# control_0_1.net
KiCad netlist of a schematic drawn in Altium Designer
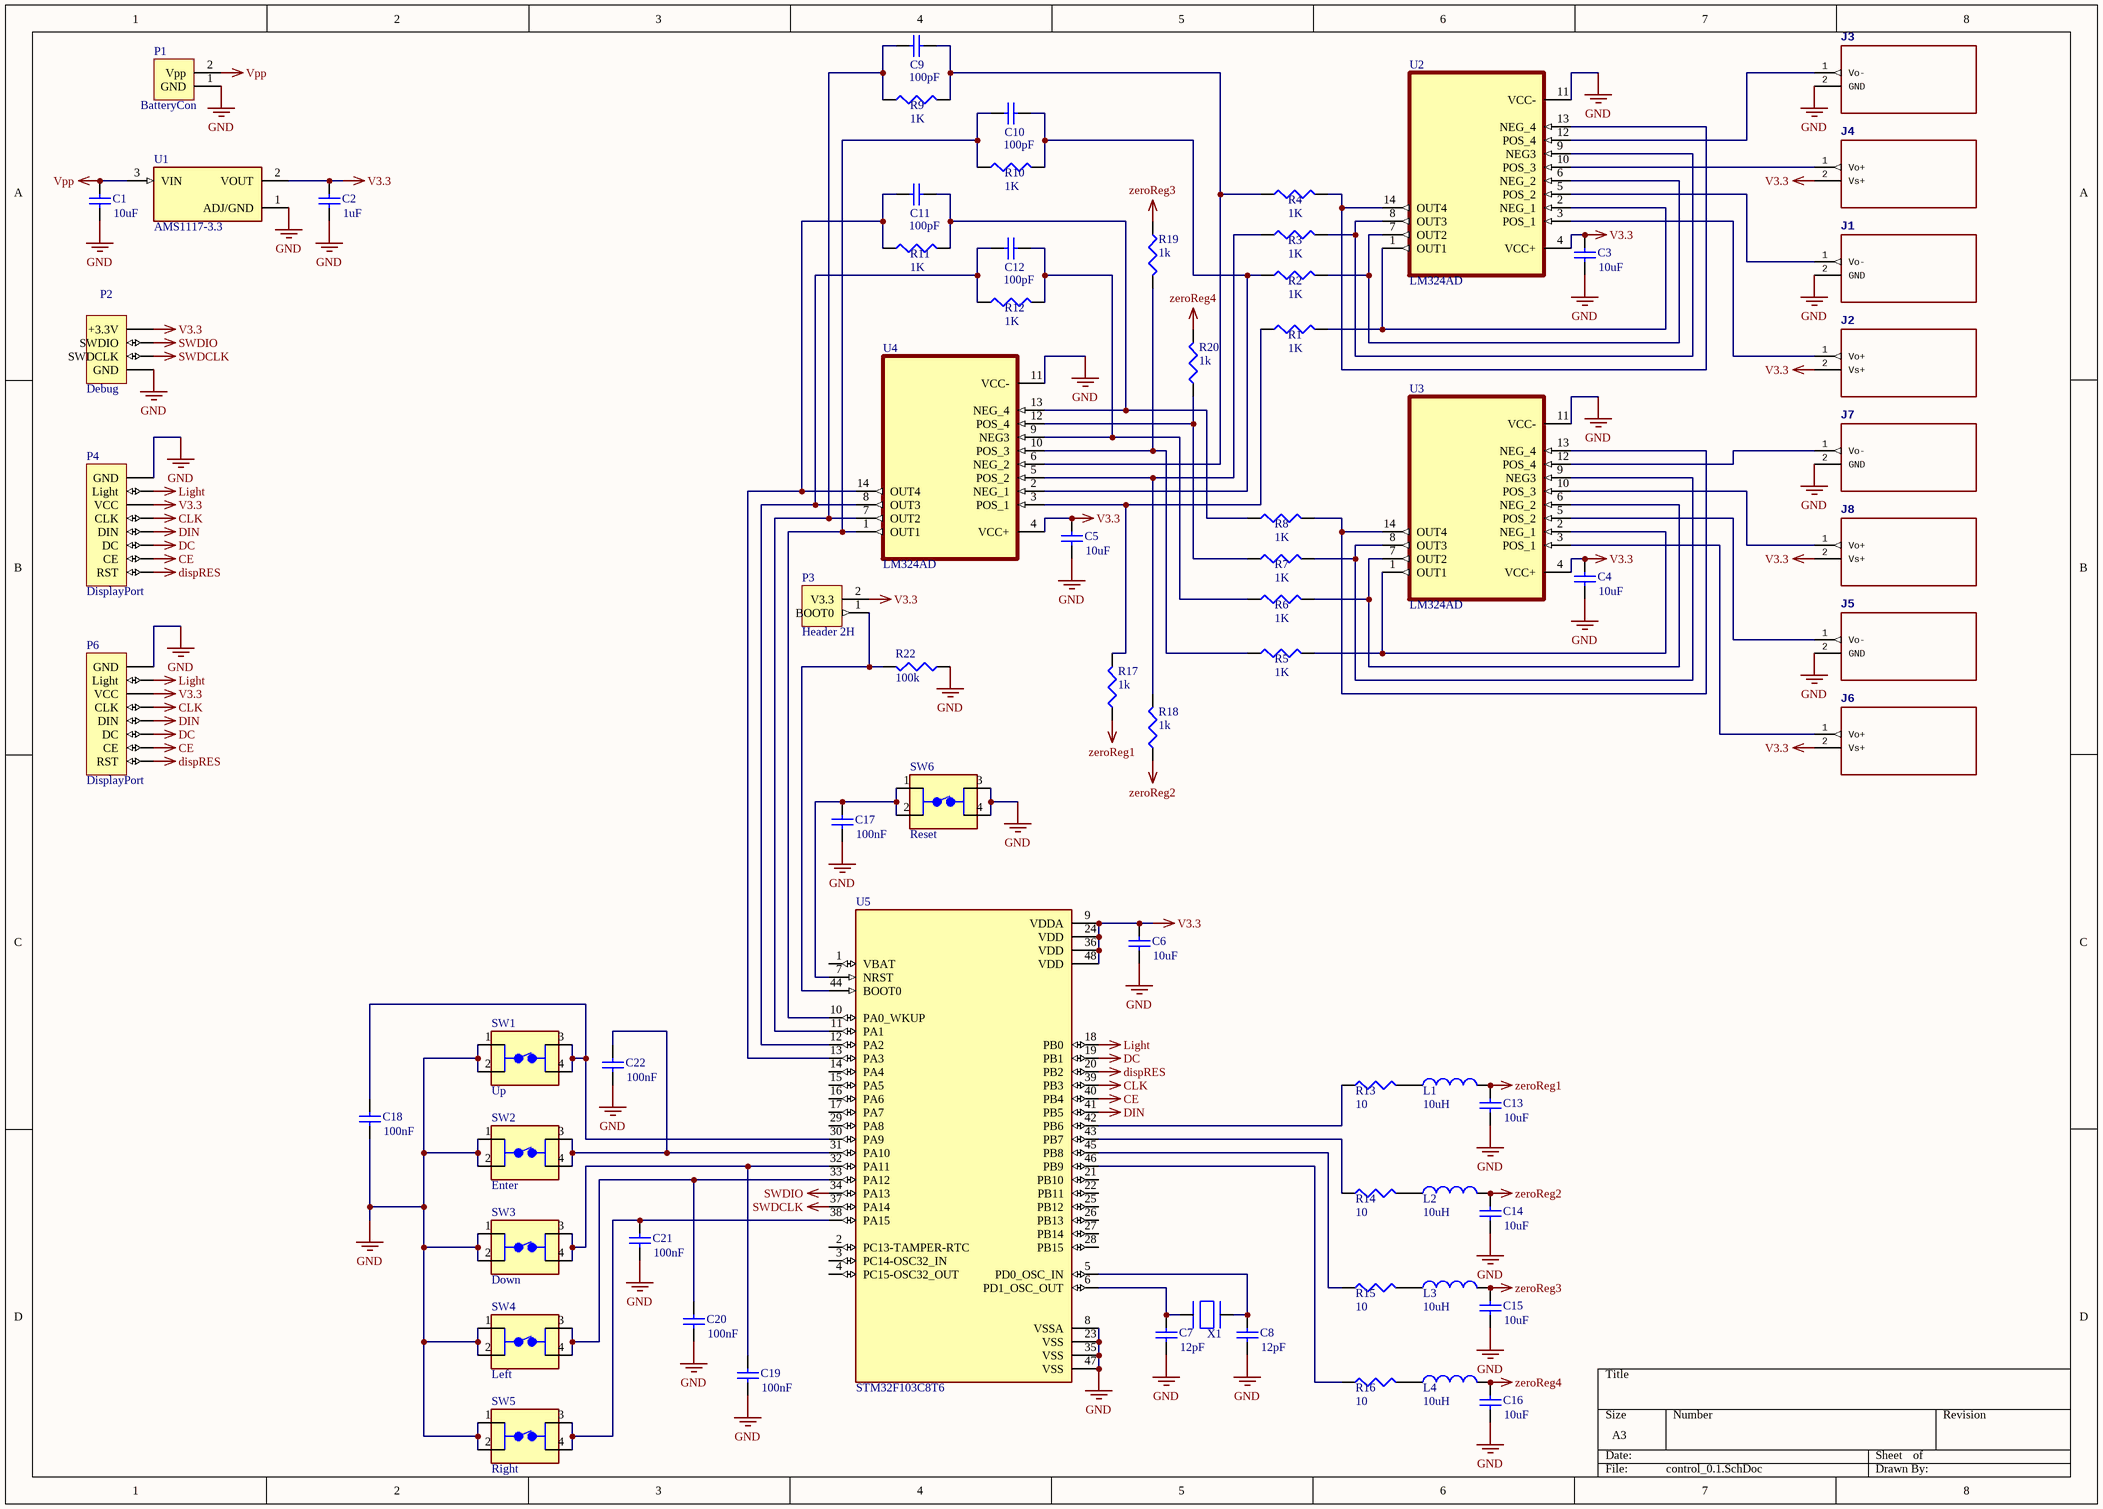
[diagram p0: control_0.1.SchDoc]

(export (version "E")
  (design (tool "Eeschema 10.0.6"))
  (components
    (comp (ref "C1")
      (value "10uF")
      (footprint "C1206")
      (description "Capacitor (Semiconductor SIM Model)")
      (fields (field (name "Comment") "Cap Semi") (field (name "PUBLISHER") "Altium Limited"))
      (libsource (lib "Miscellaneous Devices") (part "Cap Semi"))
    )
    (comp (ref "C2")
      (value "1uF")
      (footprint "C1206")
      (description "Capacitor (Semiconductor SIM Model)")
      (fields (field (name "Comment") "Cap Semi") (field (name "PUBLISHER") "Altium Limited"))
      (libsource (lib "Miscellaneous Devices") (part "Cap Semi"))
    )
    (comp (ref "C3")
      (value "10uF")
      (footprint "C1206")
      (description "Capacitor (Semiconductor SIM Model)")
      (fields (field (name "Comment") "Cap Semi") (field (name "PUBLISHER") "Altium Limited"))
      (libsource (lib "Miscellaneous Devices") (part "Cap Semi"))
    )
    (comp (ref "C4")
      (value "10uF")
      (footprint "C1206")
      (description "Capacitor (Semiconductor SIM Model)")
      (fields (field (name "Comment") "Cap Semi") (field (name "PUBLISHER") "Altium Limited"))
      (libsource (lib "Miscellaneous Devices") (part "Cap Semi"))
    )
    (comp (ref "C5")
      (value "10uF")
      (footprint "C1206")
      (description "Capacitor (Semiconductor SIM Model)")
      (fields (field (name "Comment") "Cap Semi") (field (name "PUBLISHER") "Altium Limited"))
      (libsource (lib "Miscellaneous Devices") (part "Cap Semi"))
    )
    (comp (ref "C6")
      (value "10uF")
      (footprint "C1206")
      (description "Capacitor (Semiconductor SIM Model)")
      (fields (field (name "Comment") "Cap Semi") (field (name "PUBLISHER") "Altium Limited"))
      (libsource (lib "Miscellaneous Devices") (part "Cap Semi"))
    )
    (comp (ref "C7")
      (value "12pF")
      (footprint "C1206")
      (description "Capacitor (Semiconductor SIM Model)")
      (fields (field (name "Comment") "Cap Semi") (field (name "PUBLISHER") "Altium Limited"))
      (libsource (lib "Miscellaneous Devices") (part "Cap Semi"))
    )
    (comp (ref "C8")
      (value "12pF")
      (footprint "C1206")
      (description "Capacitor (Semiconductor SIM Model)")
      (fields (field (name "Comment") "Cap Semi") (field (name "PUBLISHER") "Altium Limited"))
      (libsource (lib "Miscellaneous Devices") (part "Cap Semi"))
    )
    (comp (ref "C9")
      (value "100pF")
      (footprint "C1206")
      (description "Capacitor (Semiconductor SIM Model)")
      (fields (field (name "Comment") "Cap Semi") (field (name "PUBLISHER") "Altium Limited"))
      (libsource (lib "Miscellaneous Devices") (part "Cap Semi"))
    )
    (comp (ref "C10")
      (value "100pF")
      (footprint "C1206")
      (description "Capacitor (Semiconductor SIM Model)")
      (fields (field (name "Comment") "Cap Semi") (field (name "PUBLISHER") "Altium Limited"))
      (libsource (lib "Miscellaneous Devices") (part "Cap Semi"))
    )
    (comp (ref "C11")
      (value "100pF")
      (footprint "C1206")
      (description "Capacitor (Semiconductor SIM Model)")
      (fields (field (name "Comment") "Cap Semi") (field (name "PUBLISHER") "Altium Limited"))
      (libsource (lib "Miscellaneous Devices") (part "Cap Semi"))
    )
    (comp (ref "C12")
      (value "100pF")
      (footprint "C1206")
      (description "Capacitor (Semiconductor SIM Model)")
      (fields (field (name "Comment") "Cap Semi") (field (name "PUBLISHER") "Altium Limited"))
      (libsource (lib "Miscellaneous Devices") (part "Cap Semi"))
    )
    (comp (ref "C13")
      (value "10uF")
      (footprint "C1206")
      (description "Capacitor (Semiconductor SIM Model)")
      (fields (field (name "Comment") "Cap Semi") (field (name "PUBLISHER") "Altium Limited"))
      (libsource (lib "Miscellaneous Devices") (part "Cap Semi"))
    )
    (comp (ref "C14")
      (value "10uF")
      (footprint "C1206")
      (description "Capacitor (Semiconductor SIM Model)")
      (fields (field (name "Comment") "Cap Semi") (field (name "PUBLISHER") "Altium Limited"))
      (libsource (lib "Miscellaneous Devices") (part "Cap Semi"))
    )
    (comp (ref "C15")
      (value "10uF")
      (footprint "C1206")
      (description "Capacitor (Semiconductor SIM Model)")
      (fields (field (name "Comment") "Cap Semi") (field (name "PUBLISHER") "Altium Limited"))
      (libsource (lib "Miscellaneous Devices") (part "Cap Semi"))
    )
    (comp (ref "C16")
      (value "10uF")
      (footprint "C1206")
      (description "Capacitor (Semiconductor SIM Model)")
      (fields (field (name "Comment") "Cap Semi") (field (name "PUBLISHER") "Altium Limited"))
      (libsource (lib "Miscellaneous Devices") (part "Cap Semi"))
    )
    (comp (ref "C17")
      (value "100nF")
      (footprint "C1206")
      (description "Capacitor (Semiconductor SIM Model)")
      (fields (field (name "Comment") "Cap Semi") (field (name "PUBLISHER") "Altium Limited"))
      (libsource (lib "Miscellaneous Devices") (part "Cap Semi"))
    )
    (comp (ref "C18")
      (value "100nF")
      (footprint "C1206")
      (description "Capacitor (Semiconductor SIM Model)")
      (fields (field (name "Comment") "Cap Semi") (field (name "PUBLISHER") "Altium Limited"))
      (libsource (lib "Miscellaneous Devices") (part "Cap Semi"))
    )
    (comp (ref "C19")
      (value "100nF")
      (footprint "C1206")
      (description "Capacitor (Semiconductor SIM Model)")
      (fields (field (name "Comment") "Cap Semi") (field (name "PUBLISHER") "Altium Limited"))
      (libsource (lib "Miscellaneous Devices") (part "Cap Semi"))
    )
    (comp (ref "C20")
      (value "100nF")
      (footprint "C1206")
      (description "Capacitor (Semiconductor SIM Model)")
      (fields (field (name "Comment") "Cap Semi") (field (name "PUBLISHER") "Altium Limited"))
      (libsource (lib "Miscellaneous Devices") (part "Cap Semi"))
    )
    (comp (ref "C21")
      (value "100nF")
      (footprint "C1206")
      (description "Capacitor (Semiconductor SIM Model)")
      (fields (field (name "Comment") "Cap Semi") (field (name "PUBLISHER") "Altium Limited"))
      (libsource (lib "Miscellaneous Devices") (part "Cap Semi"))
    )
    (comp (ref "C22")
      (value "100nF")
      (footprint "C1206")
      (description "Capacitor (Semiconductor SIM Model)")
      (fields (field (name "Comment") "Cap Semi") (field (name "PUBLISHER") "Altium Limited"))
      (libsource (lib "Miscellaneous Devices") (part "Cap Semi"))
    )
    (comp (ref "J1")
      (value "SAMTEC-A-TSM-102-01-L-SHJ")
      (footprint "SAMTEC-A-TSM-102-01-L-SH")
      (libsource (lib "SAMTEC-A-TSM-102-01-L-SH") (part "SAMTEC-A-TSM-102-01-L-SHJ"))
    )
    (comp (ref "J2")
      (value "SAMTEC-A-TSM-102-01-L-SHJ")
      (footprint "SAMTEC-A-TSM-102-01-L-SH")
      (libsource (lib "SAMTEC-A-TSM-102-01-L-SH") (part "SAMTEC-A-TSM-102-01-L-SHJ"))
    )
    (comp (ref "J3")
      (value "SAMTEC-A-TSM-102-01-L-SHJ")
      (footprint "SAMTEC-A-TSM-102-01-L-SH")
      (libsource (lib "SAMTEC-A-TSM-102-01-L-SH") (part "SAMTEC-A-TSM-102-01-L-SHJ"))
    )
    (comp (ref "J4")
      (value "SAMTEC-A-TSM-102-01-L-SHJ")
      (footprint "SAMTEC-A-TSM-102-01-L-SH")
      (libsource (lib "SAMTEC-A-TSM-102-01-L-SH") (part "SAMTEC-A-TSM-102-01-L-SHJ"))
    )
    (comp (ref "J5")
      (value "SAMTEC-A-TSM-102-01-L-SHJ")
      (footprint "SAMTEC-A-TSM-102-01-L-SH")
      (libsource (lib "SAMTEC-A-TSM-102-01-L-SH") (part "SAMTEC-A-TSM-102-01-L-SHJ"))
    )
    (comp (ref "J6")
      (value "SAMTEC-A-TSM-102-01-L-SHJ")
      (footprint "SAMTEC-A-TSM-102-01-L-SH")
      (libsource (lib "SAMTEC-A-TSM-102-01-L-SH") (part "SAMTEC-A-TSM-102-01-L-SHJ"))
    )
    (comp (ref "J7")
      (value "SAMTEC-A-TSM-102-01-L-SHJ")
      (footprint "SAMTEC-A-TSM-102-01-L-SH")
      (libsource (lib "SAMTEC-A-TSM-102-01-L-SH") (part "SAMTEC-A-TSM-102-01-L-SHJ"))
    )
    (comp (ref "J8")
      (value "SAMTEC-A-TSM-102-01-L-SHJ")
      (footprint "SAMTEC-A-TSM-102-01-L-SH")
      (libsource (lib "SAMTEC-A-TSM-102-01-L-SH") (part "SAMTEC-A-TSM-102-01-L-SHJ"))
    )
    (comp (ref "L1")
      (value "10uH")
      (footprint "INDC1608L")
      (description "Inductor")
      (fields (field (name "PUBLISHER") "Altium Limited"))
      (libsource (lib "Miscellaneous Devices") (part "Inductor"))
    )
    (comp (ref "L2")
      (value "10uH")
      (footprint "INDC1608L")
      (description "Inductor")
      (fields (field (name "PUBLISHER") "Altium Limited"))
      (libsource (lib "Miscellaneous Devices") (part "Inductor"))
    )
    (comp (ref "L3")
      (value "10uH")
      (footprint "INDC1608L")
      (description "Inductor")
      (fields (field (name "PUBLISHER") "Altium Limited"))
      (libsource (lib "Miscellaneous Devices") (part "Inductor"))
    )
    (comp (ref "L4")
      (value "10uH")
      (footprint "INDC1608L")
      (description "Inductor")
      (fields (field (name "PUBLISHER") "Altium Limited"))
      (libsource (lib "Miscellaneous Devices") (part "Inductor"))
    )
    (comp (ref "P1")
      (value "BatteryCon")
      (footprint "HDR1X2H")
      (description "Header, 2-Pin, Right Angle")
      (fields (field (name "PUBLISHER") "Altium Limited"))
      (libsource (lib "Miscellaneous Connectors") (part "Header 2H"))
    )
    (comp (ref "P2")
      (value "Debug")
      (footprint "HDR1X4H")
      (description "Header, 4-Pin, Right Angle")
      (fields (field (name "PUBLISHER") "Altium Limited"))
      (libsource (lib "Miscellaneous Connectors") (part "Header 4H"))
    )
    (comp (ref "P3")
      (value "Header 2H")
      (footprint "HDR1X2H")
      (description "Header, 2-Pin, Right Angle")
      (fields (field (name "PUBLISHER") "Altium Limited"))
      (libsource (lib "Miscellaneous Connectors") (part "Header 2H"))
    )
    (comp (ref "P4")
      (value "DisplayPort")
      (footprint "HDR1X8")
      (description "Header, 8-Pin")
      (fields (field (name "PUBLISHER") "Altium Limited"))
      (libsource (lib "Miscellaneous Connectors") (part "Header 8"))
    )
    (comp (ref "P6")
      (value "DisplayPort")
      (footprint "HDR1X8")
      (description "Header, 8-Pin")
      (fields (field (name "PUBLISHER") "Altium Limited"))
      (libsource (lib "Miscellaneous Connectors") (part "Header 8"))
    )
    (comp (ref "R1")
      (value "1K")
      (footprint "14-1210")
      (description "Resistor")
      (fields (field (name "Comment") "Res3") (field (name "PUBLISHER") "Altium Limited"))
      (libsource (lib "Miscellaneous Devices") (part "Res3"))
    )
    (comp (ref "R2")
      (value "1K")
      (footprint "14-1210")
      (description "Resistor")
      (fields (field (name "Comment") "Res3") (field (name "PUBLISHER") "Altium Limited"))
      (libsource (lib "Miscellaneous Devices") (part "Res3"))
    )
    (comp (ref "R3")
      (value "1K")
      (footprint "14-1210")
      (description "Resistor")
      (fields (field (name "Comment") "Res3") (field (name "PUBLISHER") "Altium Limited"))
      (libsource (lib "Miscellaneous Devices") (part "Res3"))
    )
    (comp (ref "R4")
      (value "1K")
      (footprint "14-1210")
      (description "Resistor")
      (fields (field (name "Comment") "Res3") (field (name "PUBLISHER") "Altium Limited"))
      (libsource (lib "Miscellaneous Devices") (part "Res3"))
    )
    (comp (ref "R5")
      (value "1K")
      (footprint "14-1210")
      (description "Resistor")
      (fields (field (name "Comment") "Res3") (field (name "PUBLISHER") "Altium Limited"))
      (libsource (lib "Miscellaneous Devices") (part "Res3"))
    )
    (comp (ref "R6")
      (value "1K")
      (footprint "14-1210")
      (description "Resistor")
      (fields (field (name "Comment") "Res3") (field (name "PUBLISHER") "Altium Limited"))
      (libsource (lib "Miscellaneous Devices") (part "Res3"))
    )
    (comp (ref "R7")
      (value "1K")
      (footprint "14-1210")
      (description "Resistor")
      (fields (field (name "Comment") "Res3") (field (name "PUBLISHER") "Altium Limited"))
      (libsource (lib "Miscellaneous Devices") (part "Res3"))
    )
    (comp (ref "R8")
      (value "1K")
      (footprint "14-1210")
      (description "Resistor")
      (fields (field (name "Comment") "Res3") (field (name "PUBLISHER") "Altium Limited"))
      (libsource (lib "Miscellaneous Devices") (part "Res3"))
    )
    (comp (ref "R9")
      (value "1K")
      (footprint "14-1210")
      (description "Resistor")
      (fields (field (name "Comment") "Res3") (field (name "PUBLISHER") "Altium Limited"))
      (libsource (lib "Miscellaneous Devices") (part "Res3"))
    )
    (comp (ref "R10")
      (value "1K")
      (footprint "14-1210")
      (description "Resistor")
      (fields (field (name "Comment") "Res3") (field (name "PUBLISHER") "Altium Limited"))
      (libsource (lib "Miscellaneous Devices") (part "Res3"))
    )
    (comp (ref "R11")
      (value "1K")
      (footprint "14-1210")
      (description "Resistor")
      (fields (field (name "Comment") "Res3") (field (name "PUBLISHER") "Altium Limited"))
      (libsource (lib "Miscellaneous Devices") (part "Res3"))
    )
    (comp (ref "R12")
      (value "1K")
      (footprint "14-1210")
      (description "Resistor")
      (fields (field (name "Comment") "Res3") (field (name "PUBLISHER") "Altium Limited"))
      (libsource (lib "Miscellaneous Devices") (part "Res3"))
    )
    (comp (ref "R13")
      (value "10")
      (footprint "14-1210")
      (description "Resistor")
      (fields (field (name "Comment") "Res3") (field (name "PUBLISHER") "Altium Limited"))
      (libsource (lib "Miscellaneous Devices") (part "Res3"))
    )
    (comp (ref "R14")
      (value "10")
      (footprint "14-1210")
      (description "Resistor")
      (fields (field (name "Comment") "Res3") (field (name "PUBLISHER") "Altium Limited"))
      (libsource (lib "Miscellaneous Devices") (part "Res3"))
    )
    (comp (ref "R15")
      (value "10")
      (footprint "14-1210")
      (description "Resistor")
      (fields (field (name "Comment") "Res3") (field (name "PUBLISHER") "Altium Limited"))
      (libsource (lib "Miscellaneous Devices") (part "Res3"))
    )
    (comp (ref "R16")
      (value "10")
      (footprint "14-1210")
      (description "Resistor")
      (fields (field (name "Comment") "Res3") (field (name "PUBLISHER") "Altium Limited"))
      (libsource (lib "Miscellaneous Devices") (part "Res3"))
    )
    (comp (ref "R17")
      (value "1k")
      (footprint "14-1210")
      (description "Resistor")
      (fields (field (name "Comment") "Res3") (field (name "PUBLISHER") "Altium Limited"))
      (libsource (lib "Miscellaneous Devices") (part "Res3"))
    )
    (comp (ref "R18")
      (value "1k")
      (footprint "14-1210")
      (description "Resistor")
      (fields (field (name "Comment") "Res3") (field (name "PUBLISHER") "Altium Limited"))
      (libsource (lib "Miscellaneous Devices") (part "Res3"))
    )
    (comp (ref "R19")
      (value "1k")
      (footprint "14-1210")
      (description "Resistor")
      (fields (field (name "Comment") "Res3") (field (name "PUBLISHER") "Altium Limited"))
      (libsource (lib "Miscellaneous Devices") (part "Res3"))
    )
    (comp (ref "R20")
      (value "1k")
      (footprint "14-1210")
      (description "Resistor")
      (fields (field (name "Comment") "Res3") (field (name "PUBLISHER") "Altium Limited"))
      (libsource (lib "Miscellaneous Devices") (part "Res3"))
    )
    (comp (ref "R22")
      (value "100k")
      (footprint "14-1210")
      (description "Resistor")
      (fields (field (name "Comment") "Res3") (field (name "PUBLISHER") "Altium Limited"))
      (libsource (lib "Miscellaneous Devices") (part "Res3"))
    )
    (comp (ref "SW1")
      (value "Up")
      (footprint "TE_FSM4JSMA")
      (description "Tactile Switch SPST-NO Top Actuated Surface Mount")
      (fields (field (name "MP") "FSM4JSMA") (field (name "MF") "TE Connectivity"))
      (libsource (lib "FSM4JSMA") (part "FSM4JSMA"))
    )
    (comp (ref "SW2")
      (value "Enter")
      (footprint "TE_FSM4JSMA")
      (description "Tactile Switch SPST-NO Top Actuated Surface Mount")
      (fields (field (name "MP") "FSM4JSMA") (field (name "MF") "TE Connectivity"))
      (libsource (lib "FSM4JSMA") (part "FSM4JSMA"))
    )
    (comp (ref "SW3")
      (value "Down")
      (footprint "TE_FSM4JSMA")
      (description "Tactile Switch SPST-NO Top Actuated Surface Mount")
      (fields (field (name "MP") "FSM4JSMA") (field (name "MF") "TE Connectivity"))
      (libsource (lib "FSM4JSMA") (part "FSM4JSMA"))
    )
    (comp (ref "SW4")
      (value "Left")
      (footprint "TE_FSM4JSMA")
      (description "Tactile Switch SPST-NO Top Actuated Surface Mount")
      (fields (field (name "MP") "FSM4JSMA") (field (name "MF") "TE Connectivity"))
      (libsource (lib "FSM4JSMA") (part "FSM4JSMA"))
    )
    (comp (ref "SW5")
      (value "Right")
      (footprint "TE_FSM4JSMA")
      (description "Tactile Switch SPST-NO Top Actuated Surface Mount")
      (fields (field (name "MP") "FSM4JSMA") (field (name "MF") "TE Connectivity"))
      (libsource (lib "FSM4JSMA") (part "FSM4JSMA"))
    )
    (comp (ref "SW6")
      (value "Reset")
      (footprint "TE_FSM4JSMA")
      (description "Tactile Switch SPST-NO Top Actuated Surface Mount")
      (fields (field (name "MP") "FSM4JSMA") (field (name "MF") "TE Connectivity"))
      (libsource (lib "FSM4JSMA") (part "FSM4JSMA"))
    )
    (comp (ref "U1")
      (value "AMS1117-3.3")
      (footprint "SOT229P700X180-4N")
      (description "Sot223/Pkg 1-Amp 3.3-Volt Low Drop Out Voltage Regulatator")
      (fields (field (name "MF") "Advanced Monolithic Systems"))
      (libsource (lib "AMS1117-3.3") (part "AMS1117-3.3"))
    )
    (comp (ref "U2")
      (value "LM324AD")
      (footprint "SOIC127P600X175-14N")
      (description "Op Amp Quad Low Power Amplifier Â±15V/30V 14-Pin SOIC Tube")
      (fields (field (name "MF") "Texas Instruments"))
      (libsource (lib "LM324AD") (part "LM324AD"))
    )
    (comp (ref "U3")
      (value "LM324AD")
      (footprint "SOIC127P600X175-14N")
      (description "Op Amp Quad Low Power Amplifier Â±15V/30V 14-Pin SOIC Tube")
      (fields (field (name "MF") "Texas Instruments"))
      (libsource (lib "LM324AD") (part "LM324AD"))
    )
    (comp (ref "U4")
      (value "LM324AD")
      (footprint "SOIC127P600X175-14N")
      (description "Op Amp Quad Low Power Amplifier Â±15V/30V 14-Pin SOIC Tube")
      (fields (field (name "MF") "Texas Instruments"))
      (libsource (lib "LM324AD") (part "LM324AD"))
    )
    (comp (ref "U5")
      (value "STM32F103C8T6")
      (footprint "QFP50P900X900X160-48N")
      (description "ARMÂ® CortexÂ®-M3 STM32F1 Microcontroller IC 32-Bit 72MHz 64KB _64K x 8_ FLASH")
      (fields (field (name "MF") "STMicroelectronics"))
      (libsource (lib "STM32F103C8T6") (part "STM32F103C8T6"))
    )
    (comp (ref "X1")
      (value "ABLS-8.000MHZ-B4-T")
      (footprint "HC-49/US")
      (description "8MHz Â±30ppm Crystal 18pF 80 Ohms HC-49/US")
      (fields (field (name "MF") "Abracon LLC"))
      (libsource (lib "ABLS-8.000MHZ-B4-T") (part "ABLS-8.000MHZ-B4-T"))
    )
  )
  (nets
    (net (code "1") (name "CE") (class "Default")
      (node (ref "P4") (pin "2") (pinfunction "CE_2") (pintype "bidirectional"))
      (node (ref "P6") (pin "2") (pinfunction "CE_2") (pintype "bidirectional"))
      (node (ref "U5") (pin "40") (pinfunction "PB4_40") (pintype "bidirectional"))
    )
    (net (code "2") (name "CLK") (class "Default")
      (node (ref "P4") (pin "5") (pinfunction "CLK_5") (pintype "bidirectional"))
      (node (ref "P6") (pin "5") (pinfunction "CLK_5") (pintype "bidirectional"))
      (node (ref "U5") (pin "39") (pinfunction "PB3_39") (pintype "bidirectional"))
    )
    (net (code "3") (name "DC") (class "Default")
      (node (ref "P4") (pin "3") (pinfunction "DC_3") (pintype "bidirectional"))
      (node (ref "P6") (pin "3") (pinfunction "DC_3") (pintype "bidirectional"))
      (node (ref "U5") (pin "19") (pinfunction "PB1_19") (pintype "bidirectional"))
    )
    (net (code "4") (name "DIN") (class "Default")
      (node (ref "P4") (pin "4") (pinfunction "DIN_4") (pintype "bidirectional"))
      (node (ref "P6") (pin "4") (pinfunction "DIN_4") (pintype "bidirectional"))
      (node (ref "U5") (pin "41") (pinfunction "PB5_41") (pintype "bidirectional"))
    )
    (net (code "5") (name "GND") (class "Default")
      (node (ref "C1") (pin "1") (pinfunction "1_1") (pintype "passive"))
      (node (ref "C13") (pin "1") (pinfunction "1_1") (pintype "passive"))
      (node (ref "C14") (pin "1") (pinfunction "1_1") (pintype "passive"))
      (node (ref "C15") (pin "1") (pinfunction "1_1") (pintype "passive"))
      (node (ref "C16") (pin "1") (pinfunction "1_1") (pintype "passive"))
      (node (ref "C17") (pin "1") (pinfunction "1_1") (pintype "passive"))
      (node (ref "C18") (pin "1") (pinfunction "1_1") (pintype "passive"))
      (node (ref "C19") (pin "1") (pinfunction "1_1") (pintype "passive"))
      (node (ref "C2") (pin "1") (pinfunction "1_1") (pintype "passive"))
      (node (ref "C20") (pin "1") (pinfunction "1_1") (pintype "passive"))
      (node (ref "C21") (pin "1") (pinfunction "1_1") (pintype "passive"))
      (node (ref "C22") (pin "1") (pinfunction "1_1") (pintype "passive"))
      (node (ref "C3") (pin "1") (pinfunction "1_1") (pintype "passive"))
      (node (ref "C4") (pin "1") (pinfunction "1_1") (pintype "passive"))
      (node (ref "C5") (pin "1") (pinfunction "1_1") (pintype "passive"))
      (node (ref "C6") (pin "1") (pinfunction "1_1") (pintype "passive"))
      (node (ref "C7") (pin "1") (pinfunction "1_1") (pintype "passive"))
      (node (ref "C8") (pin "1") (pinfunction "1_1") (pintype "passive"))
      (node (ref "J1") (pin "2") (pinfunction "GND_2") (pintype "power_in"))
      (node (ref "J3") (pin "2") (pinfunction "GND_2") (pintype "power_in"))
      (node (ref "J5") (pin "2") (pinfunction "GND_2") (pintype "power_in"))
      (node (ref "J7") (pin "2") (pinfunction "GND_2") (pintype "power_in"))
      (node (ref "P1") (pin "1") (pinfunction "GND_1") (pintype "power_in"))
      (node (ref "P2") (pin "1") (pinfunction "GND_1") (pintype "power_in"))
      (node (ref "P4") (pin "8") (pinfunction "GND_8") (pintype "power_in"))
      (node (ref "P6") (pin "8") (pinfunction "GND_8") (pintype "power_in"))
      (node (ref "R22") (pin "1") (pinfunction "1_1") (pintype "passive"))
      (node (ref "SW1") (pin "1") (pinfunction "1_1") (pintype "passive"))
      (node (ref "SW1") (pin "2") (pinfunction "2_2") (pintype "passive"))
      (node (ref "SW2") (pin "1") (pinfunction "1_1") (pintype "passive"))
      (node (ref "SW2") (pin "2") (pinfunction "2_2") (pintype "passive"))
      (node (ref "SW3") (pin "1") (pinfunction "1_1") (pintype "passive"))
      (node (ref "SW3") (pin "2") (pinfunction "2_2") (pintype "passive"))
      (node (ref "SW4") (pin "1") (pinfunction "1_1") (pintype "passive"))
      (node (ref "SW4") (pin "2") (pinfunction "2_2") (pintype "passive"))
      (node (ref "SW5") (pin "1") (pinfunction "1_1") (pintype "passive"))
      (node (ref "SW5") (pin "2") (pinfunction "2_2") (pintype "passive"))
      (node (ref "SW6") (pin "3") (pinfunction "3_3") (pintype "passive"))
      (node (ref "SW6") (pin "4") (pinfunction "4_4") (pintype "passive"))
      (node (ref "U1") (pin "1") (pinfunction "ADJ/GND_1") (pintype "power_in"))
      (node (ref "U2") (pin "11") (pinfunction "VCC-_11") (pintype "power_in"))
      (node (ref "U3") (pin "11") (pinfunction "VCC-_11") (pintype "power_in"))
      (node (ref "U4") (pin "11") (pinfunction "VCC-_11") (pintype "power_in"))
      (node (ref "U5") (pin "23") (pinfunction "VSS_23") (pintype "power_in"))
      (node (ref "U5") (pin "35") (pinfunction "VSS_35") (pintype "power_in"))
      (node (ref "U5") (pin "47") (pinfunction "VSS_47") (pintype "power_in"))
      (node (ref "U5") (pin "8") (pinfunction "VSSA_8") (pintype "power_in"))
    )
    (net (code "6") (name "Light") (class "Default")
      (node (ref "P4") (pin "7") (pinfunction "Light_7") (pintype "bidirectional"))
      (node (ref "P6") (pin "7") (pinfunction "Light_7") (pintype "bidirectional"))
      (node (ref "U5") (pin "18") (pinfunction "PB0_18") (pintype "bidirectional"))
    )
    (net (code "7") (name "Net-(J1-Vo-)") (class "Default")
      (node (ref "J1") (pin "1") (pinfunction "Vo-_1") (pintype "output"))
      (node (ref "U2") (pin "5") (pinfunction "POS_2_5") (pintype "input"))
    )
    (net (code "8") (name "Net-(J2-Vo-)") (class "Default")
      (node (ref "J2") (pin "1") (pinfunction "Vo-_1") (pintype "output"))
      (node (ref "U2") (pin "3") (pinfunction "POS_1_3") (pintype "input"))
    )
    (net (code "9") (name "Net-(J3-Vo-)") (class "Default")
      (node (ref "J3") (pin "1") (pinfunction "Vo-_1") (pintype "output"))
      (node (ref "U2") (pin "12") (pinfunction "POS_4_12") (pintype "input"))
    )
    (net (code "10") (name "Net-(J4-Vo-)") (class "Default")
      (node (ref "J4") (pin "1") (pinfunction "Vo-_1") (pintype "output"))
      (node (ref "U2") (pin "10") (pinfunction "POS_3_10") (pintype "input"))
    )
    (net (code "11") (name "Net-(J5-Vo-)") (class "Default")
      (node (ref "J5") (pin "1") (pinfunction "Vo-_1") (pintype "output"))
      (node (ref "U3") (pin "5") (pinfunction "POS_2_5") (pintype "input"))
    )
    (net (code "12") (name "Net-(J6-Vo-)") (class "Default")
      (node (ref "J6") (pin "1") (pinfunction "Vo-_1") (pintype "output"))
      (node (ref "U3") (pin "3") (pinfunction "POS_1_3") (pintype "input"))
    )
    (net (code "13") (name "Net-(J7-Vo-)") (class "Default")
      (node (ref "J7") (pin "1") (pinfunction "Vo-_1") (pintype "output"))
      (node (ref "U3") (pin "12") (pinfunction "POS_4_12") (pintype "input"))
    )
    (net (code "14") (name "Net-(J8-Vo-)") (class "Default")
      (node (ref "J8") (pin "1") (pinfunction "Vo-_1") (pintype "output"))
      (node (ref "U3") (pin "10") (pinfunction "POS_3_10") (pintype "input"))
    )
    (net (code "15") (name "Net-(L1-Pad1)") (class "Default")
      (node (ref "L1") (pin "1") (pinfunction "1_1") (pintype "passive"))
      (node (ref "R13") (pin "2") (pinfunction "2_2") (pintype "passive"))
    )
    (net (code "16") (name "Net-(L2-Pad1)") (class "Default")
      (node (ref "L2") (pin "1") (pinfunction "1_1") (pintype "passive"))
      (node (ref "R14") (pin "2") (pinfunction "2_2") (pintype "passive"))
    )
    (net (code "17") (name "Net-(L3-Pad1)") (class "Default")
      (node (ref "L3") (pin "1") (pinfunction "1_1") (pintype "passive"))
      (node (ref "R15") (pin "2") (pinfunction "2_2") (pintype "passive"))
    )
    (net (code "18") (name "Net-(L4-Pad1)") (class "Default")
      (node (ref "L4") (pin "1") (pinfunction "1_1") (pintype "passive"))
      (node (ref "R16") (pin "2") (pinfunction "2_2") (pintype "passive"))
    )
    (net (code "19") (name "Net-(P3-GND)") (class "Default")
      (node (ref "P3") (pin "1") (pinfunction "GND_1") (pintype "power_in"))
      (node (ref "R22") (pin "2") (pinfunction "2_2") (pintype "passive"))
      (node (ref "U5") (pin "44") (pinfunction "BOOT0_44") (pintype "input"))
    )
    (net (code "20") (name "Net-(U2-NEG3)") (class "Default")
      (node (ref "R3") (pin "2") (pinfunction "2_2") (pintype "passive"))
      (node (ref "U2") (pin "8") (pinfunction "OUT3_8") (pintype "output"))
      (node (ref "U2") (pin "9") (pinfunction "NEG3_9") (pintype "input"))
    )
    (net (code "21") (name "Net-(U2-NEG_1)") (class "Default")
      (node (ref "R1") (pin "2") (pinfunction "2_2") (pintype "passive"))
      (node (ref "U2") (pin "1") (pinfunction "OUT1_1") (pintype "output"))
      (node (ref "U2") (pin "2") (pinfunction "NEG_1_2") (pintype "input"))
    )
    (net (code "22") (name "Net-(U2-NEG_2)") (class "Default")
      (node (ref "R2") (pin "2") (pinfunction "2_2") (pintype "passive"))
      (node (ref "U2") (pin "6") (pinfunction "NEG_2_6") (pintype "input"))
      (node (ref "U2") (pin "7") (pinfunction "OUT2_7") (pintype "output"))
    )
    (net (code "23") (name "Net-(U2-NEG_4)") (class "Default")
      (node (ref "R4") (pin "2") (pinfunction "2_2") (pintype "passive"))
      (node (ref "U2") (pin "13") (pinfunction "NEG_4_13") (pintype "input"))
      (node (ref "U2") (pin "14") (pinfunction "OUT4_14") (pintype "output"))
    )
    (net (code "24") (name "Net-(U3-NEG3)") (class "Default")
      (node (ref "R7") (pin "2") (pinfunction "2_2") (pintype "passive"))
      (node (ref "U3") (pin "8") (pinfunction "OUT3_8") (pintype "output"))
      (node (ref "U3") (pin "9") (pinfunction "NEG3_9") (pintype "input"))
    )
    (net (code "25") (name "Net-(U3-NEG_1)") (class "Default")
      (node (ref "R5") (pin "2") (pinfunction "2_2") (pintype "passive"))
      (node (ref "U3") (pin "1") (pinfunction "OUT1_1") (pintype "output"))
      (node (ref "U3") (pin "2") (pinfunction "NEG_1_2") (pintype "input"))
    )
    (net (code "26") (name "Net-(U3-NEG_2)") (class "Default")
      (node (ref "R6") (pin "2") (pinfunction "2_2") (pintype "passive"))
      (node (ref "U3") (pin "6") (pinfunction "NEG_2_6") (pintype "input"))
      (node (ref "U3") (pin "7") (pinfunction "OUT2_7") (pintype "output"))
    )
    (net (code "27") (name "Net-(U3-NEG_4)") (class "Default")
      (node (ref "R8") (pin "2") (pinfunction "2_2") (pintype "passive"))
      (node (ref "U3") (pin "13") (pinfunction "NEG_4_13") (pintype "input"))
      (node (ref "U3") (pin "14") (pinfunction "OUT4_14") (pintype "output"))
    )
    (net (code "28") (name "Net-(U4-NEG3)") (class "Default")
      (node (ref "C12") (pin "2") (pinfunction "2_2") (pintype "passive"))
      (node (ref "R12") (pin "2") (pinfunction "2_2") (pintype "passive"))
      (node (ref "R6") (pin "1") (pinfunction "1_1") (pintype "passive"))
      (node (ref "U4") (pin "9") (pinfunction "NEG3_9") (pintype "input"))
    )
    (net (code "29") (name "Net-(U4-NEG_1)") (class "Default")
      (node (ref "C10") (pin "2") (pinfunction "2_2") (pintype "passive"))
      (node (ref "R10") (pin "2") (pinfunction "2_2") (pintype "passive"))
      (node (ref "R2") (pin "1") (pinfunction "1_1") (pintype "passive"))
      (node (ref "U4") (pin "2") (pinfunction "NEG_1_2") (pintype "input"))
    )
    (net (code "30") (name "Net-(U4-NEG_2)") (class "Default")
      (node (ref "C9") (pin "2") (pinfunction "2_2") (pintype "passive"))
      (node (ref "R4") (pin "1") (pinfunction "1_1") (pintype "passive"))
      (node (ref "R9") (pin "2") (pinfunction "2_2") (pintype "passive"))
      (node (ref "U4") (pin "6") (pinfunction "NEG_2_6") (pintype "input"))
    )
    (net (code "31") (name "Net-(U4-NEG_4)") (class "Default")
      (node (ref "C11") (pin "2") (pinfunction "2_2") (pintype "passive"))
      (node (ref "R11") (pin "2") (pinfunction "2_2") (pintype "passive"))
      (node (ref "R8") (pin "1") (pinfunction "1_1") (pintype "passive"))
      (node (ref "U4") (pin "13") (pinfunction "NEG_4_13") (pintype "input"))
    )
    (net (code "32") (name "Net-(U4-OUT1)") (class "Default")
      (node (ref "C10") (pin "1") (pinfunction "1_1") (pintype "passive"))
      (node (ref "R10") (pin "1") (pinfunction "1_1") (pintype "passive"))
      (node (ref "U4") (pin "1") (pinfunction "OUT1_1") (pintype "output"))
      (node (ref "U5") (pin "10") (pinfunction "PA0_WKUP_10") (pintype "bidirectional"))
    )
    (net (code "33") (name "Net-(U4-OUT2)") (class "Default")
      (node (ref "C9") (pin "1") (pinfunction "1_1") (pintype "passive"))
      (node (ref "R9") (pin "1") (pinfunction "1_1") (pintype "passive"))
      (node (ref "U4") (pin "7") (pinfunction "OUT2_7") (pintype "output"))
      (node (ref "U5") (pin "11") (pinfunction "PA1_11") (pintype "bidirectional"))
    )
    (net (code "34") (name "Net-(U4-OUT3)") (class "Default")
      (node (ref "C12") (pin "1") (pinfunction "1_1") (pintype "passive"))
      (node (ref "R12") (pin "1") (pinfunction "1_1") (pintype "passive"))
      (node (ref "U4") (pin "8") (pinfunction "OUT3_8") (pintype "output"))
      (node (ref "U5") (pin "12") (pinfunction "PA2_12") (pintype "bidirectional"))
    )
    (net (code "35") (name "Net-(U4-OUT4)") (class "Default")
      (node (ref "C11") (pin "1") (pinfunction "1_1") (pintype "passive"))
      (node (ref "R11") (pin "1") (pinfunction "1_1") (pintype "passive"))
      (node (ref "U4") (pin "14") (pinfunction "OUT4_14") (pintype "output"))
      (node (ref "U5") (pin "13") (pinfunction "PA3_13") (pintype "bidirectional"))
    )
    (net (code "36") (name "Net-(U4-POS_1)") (class "Default")
      (node (ref "R1") (pin "1") (pinfunction "1_1") (pintype "passive"))
      (node (ref "R17") (pin "2") (pinfunction "2_2") (pintype "passive"))
      (node (ref "U4") (pin "3") (pinfunction "POS_1_3") (pintype "input"))
    )
    (net (code "37") (name "Net-(U4-POS_2)") (class "Default")
      (node (ref "R18") (pin "2") (pinfunction "2_2") (pintype "passive"))
      (node (ref "R3") (pin "1") (pinfunction "1_1") (pintype "passive"))
      (node (ref "U4") (pin "5") (pinfunction "POS_2_5") (pintype "input"))
    )
    (net (code "38") (name "Net-(U4-POS_3)") (class "Default")
      (node (ref "R19") (pin "2") (pinfunction "2_2") (pintype "passive"))
      (node (ref "R5") (pin "1") (pinfunction "1_1") (pintype "passive"))
      (node (ref "U4") (pin "10") (pinfunction "POS_3_10") (pintype "input"))
    )
    (net (code "39") (name "Net-(U4-POS_4)") (class "Default")
      (node (ref "R20") (pin "1") (pinfunction "1_1") (pintype "passive"))
      (node (ref "R7") (pin "1") (pinfunction "1_1") (pintype "passive"))
      (node (ref "U4") (pin "12") (pinfunction "POS_4_12") (pintype "input"))
    )
    (net (code "40") (name "Net-(U5-NRST)") (class "Default")
      (node (ref "C17") (pin "2") (pinfunction "2_2") (pintype "passive"))
      (node (ref "SW6") (pin "1") (pinfunction "1_1") (pintype "passive"))
      (node (ref "SW6") (pin "2") (pinfunction "2_2") (pintype "passive"))
      (node (ref "U5") (pin "7") (pinfunction "NRST_7") (pintype "input"))
    )
    (net (code "41") (name "Net-(U5-PA9)") (class "Default")
      (node (ref "C18") (pin "2") (pinfunction "2_2") (pintype "passive"))
      (node (ref "SW1") (pin "3") (pinfunction "3_3") (pintype "passive"))
      (node (ref "SW1") (pin "4") (pinfunction "4_4") (pintype "passive"))
      (node (ref "U5") (pin "30") (pinfunction "PA9_30") (pintype "bidirectional"))
    )
    (net (code "42") (name "Net-(U5-PA10)") (class "Default")
      (node (ref "C22") (pin "2") (pinfunction "2_2") (pintype "passive"))
      (node (ref "SW2") (pin "3") (pinfunction "3_3") (pintype "passive"))
      (node (ref "SW2") (pin "4") (pinfunction "4_4") (pintype "passive"))
      (node (ref "U5") (pin "31") (pinfunction "PA10_31") (pintype "bidirectional"))
    )
    (net (code "43") (name "Net-(U5-PA11)") (class "Default")
      (node (ref "C19") (pin "2") (pinfunction "2_2") (pintype "passive"))
      (node (ref "SW3") (pin "3") (pinfunction "3_3") (pintype "passive"))
      (node (ref "SW3") (pin "4") (pinfunction "4_4") (pintype "passive"))
      (node (ref "U5") (pin "32") (pinfunction "PA11_32") (pintype "bidirectional"))
    )
    (net (code "44") (name "Net-(U5-PA12)") (class "Default")
      (node (ref "C20") (pin "2") (pinfunction "2_2") (pintype "passive"))
      (node (ref "SW4") (pin "3") (pinfunction "3_3") (pintype "passive"))
      (node (ref "SW4") (pin "4") (pinfunction "4_4") (pintype "passive"))
      (node (ref "U5") (pin "33") (pinfunction "PA12_33") (pintype "bidirectional"))
    )
    (net (code "45") (name "Net-(U5-PA15)") (class "Default")
      (node (ref "C21") (pin "2") (pinfunction "2_2") (pintype "passive"))
      (node (ref "SW5") (pin "3") (pinfunction "3_3") (pintype "passive"))
      (node (ref "SW5") (pin "4") (pinfunction "4_4") (pintype "passive"))
      (node (ref "U5") (pin "38") (pinfunction "PA15_38") (pintype "bidirectional"))
    )
    (net (code "46") (name "Net-(U5-PB6)") (class "Default")
      (node (ref "R13") (pin "1") (pinfunction "1_1") (pintype "passive"))
      (node (ref "U5") (pin "42") (pinfunction "PB6_42") (pintype "bidirectional"))
    )
    (net (code "47") (name "Net-(U5-PB7)") (class "Default")
      (node (ref "R14") (pin "1") (pinfunction "1_1") (pintype "passive"))
      (node (ref "U5") (pin "43") (pinfunction "PB7_43") (pintype "bidirectional"))
    )
    (net (code "48") (name "Net-(U5-PB8)") (class "Default")
      (node (ref "R15") (pin "1") (pinfunction "1_1") (pintype "passive"))
      (node (ref "U5") (pin "45") (pinfunction "PB8_45") (pintype "bidirectional"))
    )
    (net (code "49") (name "Net-(U5-PB9)") (class "Default")
      (node (ref "R16") (pin "1") (pinfunction "1_1") (pintype "passive"))
      (node (ref "U5") (pin "46") (pinfunction "PB9_46") (pintype "bidirectional"))
    )
    (net (code "50") (name "Net-(U5-PD0_OSC_IN)") (class "Default")
      (node (ref "C8") (pin "2") (pinfunction "2_2") (pintype "passive"))
      (node (ref "U5") (pin "5") (pinfunction "PD0_OSC_IN_5") (pintype "bidirectional"))
      (node (ref "X1") (pin "P$2") (pinfunction "3_P$2") (pintype "bidirectional"))
    )
    (net (code "51") (name "Net-(U5-PD1_OSC_OUT)") (class "Default")
      (node (ref "C7") (pin "2") (pinfunction "2_2") (pintype "passive"))
      (node (ref "U5") (pin "6") (pinfunction "PD1_OSC_OUT_6") (pintype "bidirectional"))
      (node (ref "X1") (pin "P$1") (pinfunction "1_P$1") (pintype "bidirectional"))
    )
    (net (code "52") (name "SWDCLK") (class "Default")
      (node (ref "P2") (pin "2") (pinfunction "SWDCLK_2") (pintype "bidirectional"))
      (node (ref "U5") (pin "37") (pinfunction "PA14_37") (pintype "bidirectional"))
    )
    (net (code "53") (name "SWDIO") (class "Default")
      (node (ref "P2") (pin "3") (pinfunction "SWDIO_3") (pintype "bidirectional"))
      (node (ref "U5") (pin "34") (pinfunction "PA13_34") (pintype "bidirectional"))
    )
    (net (code "54") (name "V3.3") (class "Default")
      (node (ref "C2") (pin "2") (pinfunction "2_2") (pintype "passive"))
      (node (ref "C3") (pin "2") (pinfunction "2_2") (pintype "passive"))
      (node (ref "C4") (pin "2") (pinfunction "2_2") (pintype "passive"))
      (node (ref "C5") (pin "2") (pinfunction "2_2") (pintype "passive"))
      (node (ref "C6") (pin "2") (pinfunction "2_2") (pintype "passive"))
      (node (ref "J2") (pin "2") (pinfunction "GND_2") (pintype "power_in"))
      (node (ref "J4") (pin "2") (pinfunction "GND_2") (pintype "power_in"))
      (node (ref "J6") (pin "2") (pinfunction "GND_2") (pintype "power_in"))
      (node (ref "J8") (pin "2") (pinfunction "GND_2") (pintype "power_in"))
      (node (ref "P2") (pin "4") (pinfunction "+3.3V_4") (pintype "power_in"))
      (node (ref "P3") (pin "2") (pinfunction "Vpp_2") (pintype "power_in"))
      (node (ref "P4") (pin "6") (pinfunction "VCC_6") (pintype "power_in"))
      (node (ref "P6") (pin "6") (pinfunction "VCC_6") (pintype "power_in"))
      (node (ref "U1") (pin "2") (pinfunction "VOUT_2") (pintype "power_in"))
      (node (ref "U2") (pin "4") (pinfunction "VCC+_4") (pintype "power_in"))
      (node (ref "U3") (pin "4") (pinfunction "VCC+_4") (pintype "power_in"))
      (node (ref "U4") (pin "4") (pinfunction "VCC+_4") (pintype "power_in"))
      (node (ref "U5") (pin "24") (pinfunction "VDD_24") (pintype "power_in"))
      (node (ref "U5") (pin "36") (pinfunction "VDD_36") (pintype "power_in"))
      (node (ref "U5") (pin "48") (pinfunction "VDD_48") (pintype "power_in"))
      (node (ref "U5") (pin "9") (pinfunction "VDDA_9") (pintype "power_in"))
    )
    (net (code "55") (name "Vpp") (class "Default")
      (node (ref "C1") (pin "2") (pinfunction "2_2") (pintype "passive"))
      (node (ref "P1") (pin "2") (pinfunction "Vpp_2") (pintype "power_in"))
      (node (ref "U1") (pin "3") (pinfunction "VIN_3") (pintype "input"))
    )
    (net (code "56") (name "dispRES") (class "Default")
      (node (ref "P4") (pin "1") (pinfunction "RST_1") (pintype "bidirectional"))
      (node (ref "P6") (pin "1") (pinfunction "RST_1") (pintype "bidirectional"))
      (node (ref "U5") (pin "20") (pinfunction "PB2_20") (pintype "bidirectional"))
    )
    (net (code "57") (name "unconnected-(U5-PA4-Pad14)") (class "Default")
      (node (ref "U5") (pin "14") (pinfunction "PA4_14") (pintype "bidirectional"))
    )
    (net (code "58") (name "unconnected-(U5-PA5-Pad15)") (class "Default")
      (node (ref "U5") (pin "15") (pinfunction "PA5_15") (pintype "bidirectional"))
    )
    (net (code "59") (name "unconnected-(U5-PA6-Pad16)") (class "Default")
      (node (ref "U5") (pin "16") (pinfunction "PA6_16") (pintype "bidirectional"))
    )
    (net (code "60") (name "unconnected-(U5-PA7-Pad17)") (class "Default")
      (node (ref "U5") (pin "17") (pinfunction "PA7_17") (pintype "bidirectional"))
    )
    (net (code "61") (name "unconnected-(U5-PA8-Pad29)") (class "Default")
      (node (ref "U5") (pin "29") (pinfunction "PA8_29") (pintype "bidirectional"))
    )
    (net (code "62") (name "unconnected-(U5-PB10-Pad21)") (class "Default")
      (node (ref "U5") (pin "21") (pinfunction "PB10_21") (pintype "bidirectional"))
    )
    (net (code "63") (name "unconnected-(U5-PB11-Pad22)") (class "Default")
      (node (ref "U5") (pin "22") (pinfunction "PB11_22") (pintype "bidirectional"))
    )
    (net (code "64") (name "unconnected-(U5-PB12-Pad25)") (class "Default")
      (node (ref "U5") (pin "25") (pinfunction "PB12_25") (pintype "bidirectional"))
    )
    (net (code "65") (name "unconnected-(U5-PB13-Pad26)") (class "Default")
      (node (ref "U5") (pin "26") (pinfunction "PB13_26") (pintype "bidirectional"))
    )
    (net (code "66") (name "unconnected-(U5-PB14-Pad27)") (class "Default")
      (node (ref "U5") (pin "27") (pinfunction "PB14_27") (pintype "bidirectional"))
    )
    (net (code "67") (name "unconnected-(U5-PB15-Pad28)") (class "Default")
      (node (ref "U5") (pin "28") (pinfunction "PB15_28") (pintype "bidirectional"))
    )
    (net (code "68") (name "unconnected-(U5-PC13-TAMPER-RTC-Pad2)") (class "Default")
      (node (ref "U5") (pin "2") (pinfunction "PC13-TAMPER-RTC_2") (pintype "bidirectional"))
    )
    (net (code "69") (name "unconnected-(U5-PC14-OSC32_IN-Pad3)") (class "Default")
      (node (ref "U5") (pin "3") (pinfunction "PC14-OSC32_IN_3") (pintype "bidirectional"))
    )
    (net (code "70") (name "unconnected-(U5-PC15-OSC32_OUT-Pad4)") (class "Default")
      (node (ref "U5") (pin "4") (pinfunction "PC15-OSC32_OUT_4") (pintype "bidirectional"))
    )
    (net (code "71") (name "unconnected-(U5-VBAT-Pad1)") (class "Default")
      (node (ref "U5") (pin "1") (pinfunction "VBAT_1") (pintype "bidirectional"))
    )
    (net (code "72") (name "zeroReg1") (class "Default")
      (node (ref "C13") (pin "2") (pinfunction "2_2") (pintype "passive"))
      (node (ref "L1") (pin "2") (pinfunction "2_2") (pintype "passive"))
      (node (ref "R17") (pin "1") (pinfunction "1_1") (pintype "passive"))
    )
    (net (code "73") (name "zeroReg2") (class "Default")
      (node (ref "C14") (pin "2") (pinfunction "2_2") (pintype "passive"))
      (node (ref "L2") (pin "2") (pinfunction "2_2") (pintype "passive"))
      (node (ref "R18") (pin "1") (pinfunction "1_1") (pintype "passive"))
    )
    (net (code "74") (name "zeroReg3") (class "Default")
      (node (ref "C15") (pin "2") (pinfunction "2_2") (pintype "passive"))
      (node (ref "L3") (pin "2") (pinfunction "2_2") (pintype "passive"))
      (node (ref "R19") (pin "1") (pinfunction "1_1") (pintype "passive"))
    )
    (net (code "75") (name "zeroReg4") (class "Default")
      (node (ref "C16") (pin "2") (pinfunction "2_2") (pintype "passive"))
      (node (ref "L4") (pin "2") (pinfunction "2_2") (pintype "passive"))
      (node (ref "R20") (pin "2") (pinfunction "2_2") (pintype "passive"))
    )
  )
)
